# akabeacon_mini_da14580.net
KiCad netlist of a schematic drawn in EAGLE
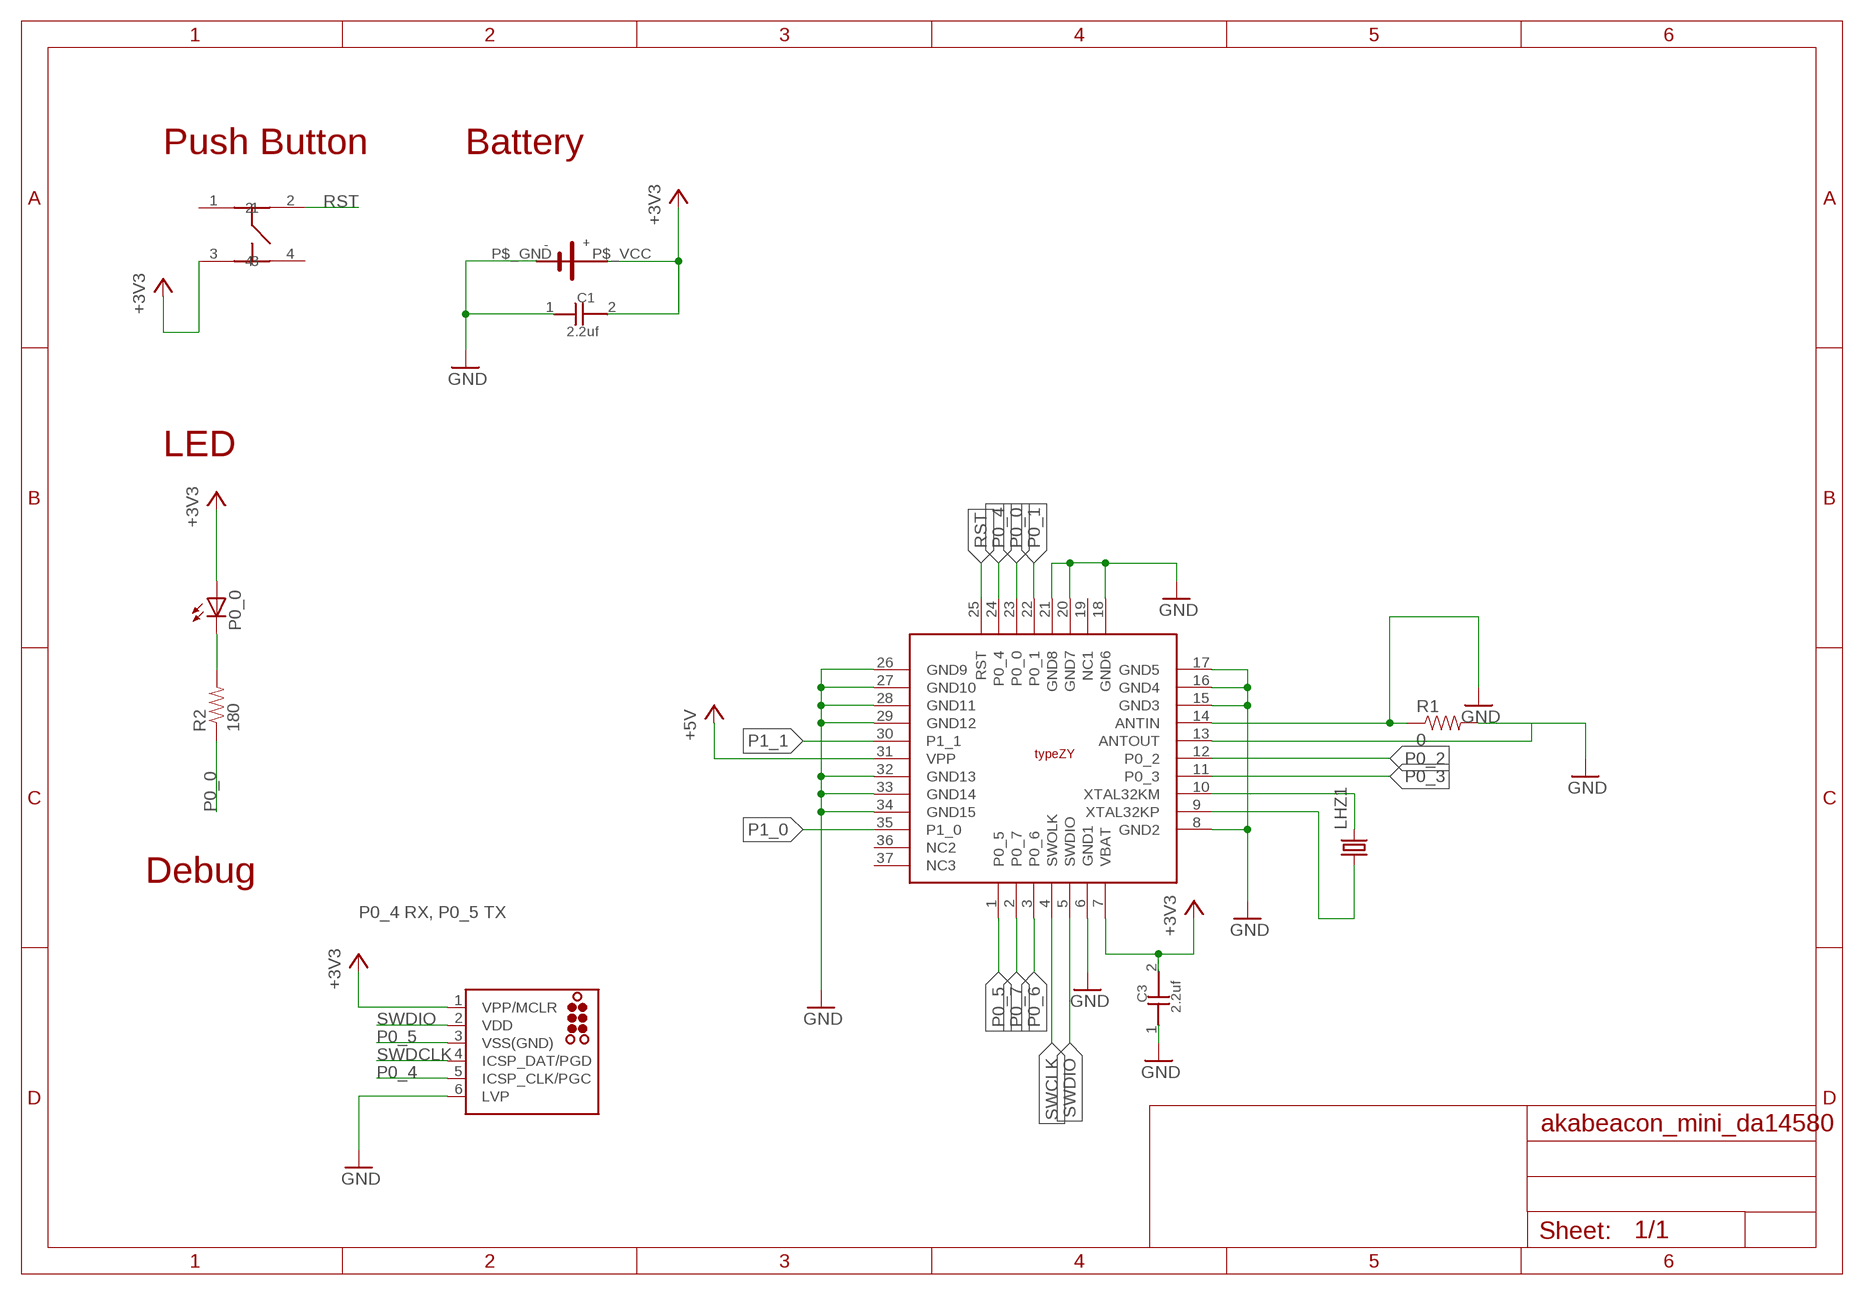
[diagram p0: schematic, sheet 1]

(export (version "E")
  (design (tool "Eeschema 10.0.6"))
  (components
    (comp (ref "C1")
      (value "2.2uf")
      (footprint "eagle-import:0603")
      (libsource (lib "eagle-import") (part "CAPACITOR0603"))
    )
    (comp (ref "C3")
      (value "2.2uf")
      (footprint "eagle-import:0603")
      (libsource (lib "eagle-import") (part "CAPACITOR0603"))
    )
    (comp (ref "J2")
      (value "TC2030-MCP")
      (footprint "eagle-import:TC2030-MCP")
      (libsource (lib "eagle-import") (part "TC2030-MCP"))
    )
    (comp (ref "LHZ1")
      (value "FC-12M")
      (footprint "eagle-import:FC-12M")
      (libsource (lib "eagle-import") (part "FC-12M"))
    )
    (comp (ref "P0_0")
      (value "LEDCHIP-LED0603")
      (footprint "eagle-import:CHIP-LED0603")
      (libsource (lib "eagle-import") (part "LEDCHIP-LED0603"))
    )
    (comp (ref "R1")
      (value "0")
      (footprint "eagle-import:0603-RES")
      (libsource (lib "eagle-import") (part "RESISTOR0603-RES"))
    )
    (comp (ref "R2")
      (value "180")
      (footprint "eagle-import:0603-RES")
      (libsource (lib "eagle-import") (part "RESISTOR0603-RES"))
    )
    (comp (ref "U$1")
      (value "MURATA-TYPEZY")
      (footprint "eagle-import:MURATA_TYPEZY")
      (libsource (lib "eagle-import") (part "MURATA-TYPEZY"))
    )
    (comp (ref "U$6")
      (value "SMTU2450-BOTTOM-MINI")
      (footprint "eagle-import:SMTU2450-BOTTOM-MINI")
      (libsource (lib "eagle-import") (part "SMTU2450-BOTTOM-MINI"))
    )
    (comp (ref "U$7")
      (value "SWICTH-4P(KMR2)")
      (footprint "eagle-import:SWITCH-4P(KMR2)")
      (libsource (lib "eagle-import") (part "SWICTH-4P(KMR2)"))
    )
  )
  (nets
    (net (code "1") (name "+3V3") (class "Default")
      (node (ref "C1") (pin "2") (pinfunction "2_2") (pintype "passive"))
      (node (ref "C3") (pin "2") (pinfunction "2_2") (pintype "passive"))
      (node (ref "J2") (pin "1") (pinfunction "VPP/MCLR_1") (pintype "passive"))
      (node (ref "P0_0") (pin "A") (pinfunction "A_A") (pintype "passive"))
      (node (ref "U$1") (pin "7") (pinfunction "VBAT_7") (pintype "bidirectional"))
      (node (ref "U$6") (pin "P$_VCC") (pinfunction "P$_VCC_P$_VCC") (pintype "bidirectional"))
      (node (ref "U$7") (pin "3") (pinfunction "3_3") (pintype "bidirectional"))
    )
    (net (code "2") (name "+5V") (class "Default")
      (node (ref "U$1") (pin "31") (pinfunction "VPP_31") (pintype "bidirectional"))
    )
    (net (code "3") (name "/SWDCLK") (class "Default")
      (node (ref "J2") (pin "4") (pinfunction "ICSP_DAT/PGD_4") (pintype "bidirectional"))
    )
    (net (code "4") (name "GND") (class "Default")
      (node (ref "C1") (pin "1") (pinfunction "1_1") (pintype "passive"))
      (node (ref "C3") (pin "1") (pinfunction "1_1") (pintype "passive"))
      (node (ref "J2") (pin "6") (pinfunction "LVP_6") (pintype "bidirectional"))
      (node (ref "R1") (pin "1") (pinfunction "1_1") (pintype "passive"))
      (node (ref "R1") (pin "2") (pinfunction "2_2") (pintype "passive"))
      (node (ref "U$1") (pin "14") (pinfunction "ANTIN_14") (pintype "bidirectional"))
      (node (ref "U$1") (pin "15") (pinfunction "GND3_15") (pintype "bidirectional"))
      (node (ref "U$1") (pin "16") (pinfunction "GND4_16") (pintype "bidirectional"))
      (node (ref "U$1") (pin "17") (pinfunction "GND5_17") (pintype "bidirectional"))
      (node (ref "U$1") (pin "18") (pinfunction "GND6_18") (pintype "bidirectional"))
      (node (ref "U$1") (pin "20") (pinfunction "GND7_20") (pintype "bidirectional"))
      (node (ref "U$1") (pin "21") (pinfunction "GND8_21") (pintype "bidirectional"))
      (node (ref "U$1") (pin "26") (pinfunction "GND9_26") (pintype "bidirectional"))
      (node (ref "U$1") (pin "27") (pinfunction "GND10_27") (pintype "bidirectional"))
      (node (ref "U$1") (pin "28") (pinfunction "GND11_28") (pintype "bidirectional"))
      (node (ref "U$1") (pin "29") (pinfunction "GND12_29") (pintype "bidirectional"))
      (node (ref "U$1") (pin "32") (pinfunction "GND13_32") (pintype "bidirectional"))
      (node (ref "U$1") (pin "33") (pinfunction "GND14_33") (pintype "bidirectional"))
      (node (ref "U$1") (pin "34") (pinfunction "GND15_34") (pintype "bidirectional"))
      (node (ref "U$1") (pin "6") (pinfunction "GND1_6") (pintype "bidirectional"))
      (node (ref "U$1") (pin "8") (pinfunction "GND2_8") (pintype "bidirectional"))
      (node (ref "U$6") (pin "P$_GND") (pinfunction "P$_GND_P$_GND") (pintype "bidirectional"))
    )
    (net (code "5") (name "Net-(P0_0-PadC)") (class "Default")
      (node (ref "P0_0") (pin "C") (pinfunction "C_C") (pintype "passive"))
      (node (ref "R2") (pin "2") (pinfunction "2_2") (pintype "passive"))
    )
    (net (code "6") (name "Net-(U$1-XTAL32KM)") (class "Default")
      (node (ref "LHZ1") (pin "2") (pinfunction "2_2") (pintype "passive"))
      (node (ref "U$1") (pin "10") (pinfunction "XTAL32KM_10") (pintype "bidirectional"))
    )
    (net (code "7") (name "Net-(U$1-XTAL32KP)") (class "Default")
      (node (ref "LHZ1") (pin "1") (pinfunction "1_1") (pintype "passive"))
      (node (ref "U$1") (pin "9") (pinfunction "XTAL32KP_9") (pintype "bidirectional"))
    )
    (net (code "8") (name "P0_0") (class "Default")
      (node (ref "R2") (pin "1") (pinfunction "1_1") (pintype "passive"))
      (node (ref "U$1") (pin "23") (pinfunction "P0_0_23") (pintype "bidirectional"))
    )
    (net (code "9") (name "P0_1") (class "Default")
      (node (ref "U$1") (pin "22") (pinfunction "P0_1_22") (pintype "bidirectional"))
    )
    (net (code "10") (name "P0_2") (class "Default")
      (node (ref "U$1") (pin "12") (pinfunction "P0_2_12") (pintype "bidirectional"))
    )
    (net (code "11") (name "P0_3") (class "Default")
      (node (ref "U$1") (pin "11") (pinfunction "P0_3_11") (pintype "bidirectional"))
    )
    (net (code "12") (name "P0_4") (class "Default")
      (node (ref "J2") (pin "5") (pinfunction "ICSP_CLK/PGC_5") (pintype "output"))
      (node (ref "U$1") (pin "24") (pinfunction "P0_4_24") (pintype "bidirectional"))
    )
    (net (code "13") (name "P0_5") (class "Default")
      (node (ref "J2") (pin "3") (pinfunction "VSS(GND)_3") (pintype "power_in"))
      (node (ref "U$1") (pin "1") (pinfunction "P0_5_1") (pintype "bidirectional"))
    )
    (net (code "14") (name "P0_6") (class "Default")
      (node (ref "U$1") (pin "3") (pinfunction "P0_6_3") (pintype "bidirectional"))
    )
    (net (code "15") (name "P0_7") (class "Default")
      (node (ref "U$1") (pin "2") (pinfunction "P0_7_2") (pintype "bidirectional"))
    )
    (net (code "16") (name "P1_0") (class "Default")
      (node (ref "U$1") (pin "35") (pinfunction "P1_0_35") (pintype "bidirectional"))
    )
    (net (code "17") (name "P1_1") (class "Default")
      (node (ref "U$1") (pin "30") (pinfunction "P1_1_30") (pintype "bidirectional"))
    )
    (net (code "18") (name "RST") (class "Default")
      (node (ref "U$1") (pin "25") (pinfunction "RST_25") (pintype "bidirectional"))
      (node (ref "U$7") (pin "2") (pinfunction "2_2") (pintype "bidirectional"))
    )
    (net (code "19") (name "SWCLK") (class "Default")
      (node (ref "U$1") (pin "4") (pinfunction "SWOLK_4") (pintype "bidirectional"))
    )
    (net (code "20") (name "SWDIO") (class "Default")
      (node (ref "J2") (pin "2") (pinfunction "VDD_2") (pintype "power_in"))
      (node (ref "U$1") (pin "5") (pinfunction "SWDIO_5") (pintype "bidirectional"))
    )
    (net (code "21") (name "unconnected-(U$1-ANTOUT-Pad13)") (class "Default")
      (node (ref "U$1") (pin "13") (pinfunction "ANTOUT_13") (pintype "bidirectional"))
    )
    (net (code "22") (name "unconnected-(U$1-NC1-Pad19)") (class "Default")
      (node (ref "U$1") (pin "19") (pinfunction "NC1_19") (pintype "bidirectional"))
    )
    (net (code "23") (name "unconnected-(U$1-NC2-Pad36)") (class "Default")
      (node (ref "U$1") (pin "36") (pinfunction "NC2_36") (pintype "bidirectional"))
    )
    (net (code "24") (name "unconnected-(U$1-NC3-Pad37)") (class "Default")
      (node (ref "U$1") (pin "37") (pinfunction "NC3_37") (pintype "bidirectional"))
    )
    (net (code "25") (name "unconnected-(U$7-Pad1)") (class "Default")
      (node (ref "U$7") (pin "1") (pinfunction "1_1") (pintype "bidirectional"))
    )
    (net (code "26") (name "unconnected-(U$7-Pad4)") (class "Default")
      (node (ref "U$7") (pin "4") (pinfunction "4_4") (pintype "bidirectional"))
    )
  )
)
